# schematic.net
KiCad netlist of a schematic drawn in EAGLE
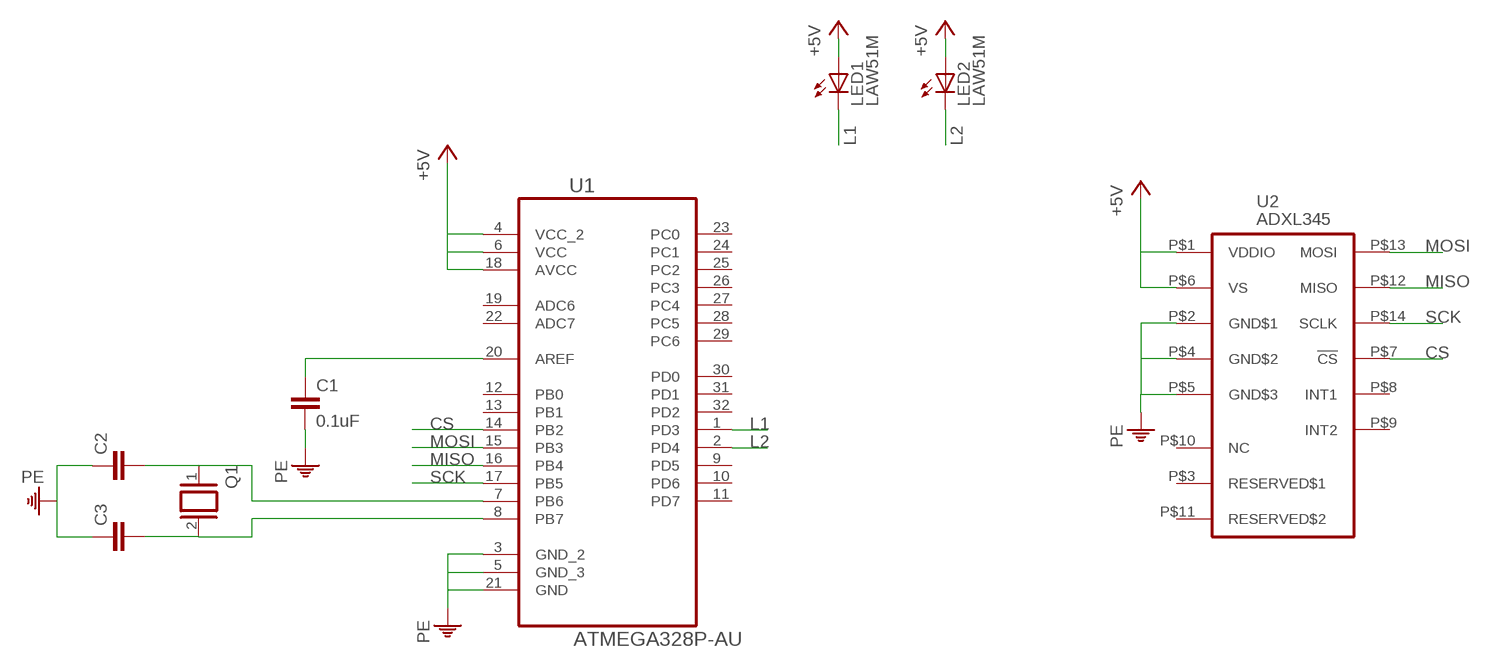
[diagram p0: schematic, sheet 1]

(export (version "E")
  (design (tool "Eeschema 10.0.6"))
  (components
    (comp (ref "C1")
      (value "0.1uF")
      (footprint "eagle-import:C2.5-3")
      (libsource (lib "eagle-import") (part "C2,5-3"))
    )
    (comp (ref "C2")
      (value "C2,5-3")
      (footprint "eagle-import:C2.5-3")
      (libsource (lib "eagle-import") (part "C2,5-3"))
    )
    (comp (ref "C3")
      (value "C2,5-3")
      (footprint "eagle-import:C2.5-3")
      (libsource (lib "eagle-import") (part "C2,5-3"))
    )
    (comp (ref "LED1")
      (value "LAW51M")
      (footprint "eagle-import:W51")
      (libsource (lib "eagle-import") (part "W51MLA"))
    )
    (comp (ref "LED2")
      (value "LAW51M")
      (footprint "eagle-import:W51")
      (libsource (lib "eagle-import") (part "W51MLA"))
    )
    (comp (ref "Q1")
      (value "XTAL/S")
      (footprint "eagle-import:QS")
      (libsource (lib "eagle-import") (part "XTAL/S"))
    )
    (comp (ref "U1")
      (value "ATMEGA328P-AU")
      (footprint "eagle-import:QFP80P900X900X120-32N")
      (libsource (lib "eagle-import") (part "ATMEGA328P-AU"))
    )
    (comp (ref "U2")
      (value "ADXL345")
      (footprint "eagle-import:LGA14")
      (libsource (lib "eagle-import") (part "ADXL345"))
    )
  )
  (nets
    (net (code "1") (name "+5V") (class "Default")
      (node (ref "LED1") (pin "A") (pinfunction "A_A") (pintype "passive"))
      (node (ref "LED2") (pin "A") (pinfunction "A_A") (pintype "passive"))
      (node (ref "U1") (pin "18") (pinfunction "AVCC_18") (pintype "power_in"))
      (node (ref "U1") (pin "4") (pinfunction "VCC_2_4") (pintype "power_in"))
      (node (ref "U1") (pin "6") (pinfunction "VCC_6") (pintype "power_in"))
      (node (ref "U2") (pin "P$1") (pinfunction "VDDIO_P$1") (pintype "power_in"))
      (node (ref "U2") (pin "P$6") (pinfunction "VS_P$6") (pintype "power_in"))
    )
    (net (code "2") (name "/CS") (class "Default")
      (node (ref "U1") (pin "14") (pinfunction "PB2_14") (pintype "bidirectional"))
      (node (ref "U2") (pin "P$7") (pinfunction "~{CS}_P$7") (pintype "input"))
    )
    (net (code "3") (name "/L1") (class "Default")
      (node (ref "LED1") (pin "C") (pinfunction "C_C") (pintype "passive"))
      (node (ref "U1") (pin "1") (pinfunction "PD3_1") (pintype "bidirectional"))
    )
    (net (code "4") (name "/L2") (class "Default")
      (node (ref "LED2") (pin "C") (pinfunction "C_C") (pintype "passive"))
      (node (ref "U1") (pin "2") (pinfunction "PD4_2") (pintype "bidirectional"))
    )
    (net (code "5") (name "/MISO") (class "Default")
      (node (ref "U1") (pin "16") (pinfunction "PB4_16") (pintype "bidirectional"))
      (node (ref "U2") (pin "P$12") (pinfunction "MISO_P$12") (pintype "output"))
    )
    (net (code "6") (name "/MOSI") (class "Default")
      (node (ref "U1") (pin "15") (pinfunction "PB3_15") (pintype "bidirectional"))
      (node (ref "U2") (pin "P$13") (pinfunction "MOSI_P$13") (pintype "input"))
    )
    (net (code "7") (name "/SCK") (class "Default")
      (node (ref "U1") (pin "17") (pinfunction "PB5_17") (pintype "bidirectional"))
      (node (ref "U2") (pin "P$14") (pinfunction "SCLK_P$14") (pintype "input"))
    )
    (net (code "8") (name "Net-(U1-AREF)") (class "Default")
      (node (ref "C1") (pin "1") (pinfunction "1_1") (pintype "passive"))
      (node (ref "U1") (pin "20") (pinfunction "AREF_20") (pintype "input"))
    )
    (net (code "9") (name "Net-(U1-PB6)") (class "Default")
      (node (ref "C2") (pin "2") (pinfunction "2_2") (pintype "passive"))
      (node (ref "Q1") (pin "1") (pinfunction "1_1") (pintype "passive"))
      (node (ref "U1") (pin "7") (pinfunction "PB6_7") (pintype "bidirectional"))
    )
    (net (code "10") (name "Net-(U1-PB7)") (class "Default")
      (node (ref "C3") (pin "2") (pinfunction "2_2") (pintype "passive"))
      (node (ref "Q1") (pin "2") (pinfunction "2_2") (pintype "passive"))
      (node (ref "U1") (pin "8") (pinfunction "PB7_8") (pintype "bidirectional"))
    )
    (net (code "11") (name "PE") (class "Default")
      (node (ref "C1") (pin "2") (pinfunction "2_2") (pintype "passive"))
      (node (ref "C2") (pin "1") (pinfunction "1_1") (pintype "passive"))
      (node (ref "C3") (pin "1") (pinfunction "1_1") (pintype "passive"))
      (node (ref "U1") (pin "21") (pinfunction "GND_21") (pintype "passive"))
      (node (ref "U1") (pin "3") (pinfunction "GND_2_3") (pintype "passive"))
      (node (ref "U1") (pin "5") (pinfunction "GND_3_5") (pintype "passive"))
      (node (ref "U2") (pin "P$2") (pinfunction "GND$1_P$2") (pintype "power_in"))
      (node (ref "U2") (pin "P$4") (pinfunction "GND$2_P$4") (pintype "power_in"))
      (node (ref "U2") (pin "P$5") (pinfunction "GND$3_P$5") (pintype "power_in"))
    )
    (net (code "12") (name "unconnected-(U1-ADC6-Pad19)") (class "Default")
      (node (ref "U1") (pin "19") (pinfunction "ADC6_19") (pintype "input"))
    )
    (net (code "13") (name "unconnected-(U1-ADC7-Pad22)") (class "Default")
      (node (ref "U1") (pin "22") (pinfunction "ADC7_22") (pintype "input"))
    )
    (net (code "14") (name "unconnected-(U1-PB0-Pad12)") (class "Default")
      (node (ref "U1") (pin "12") (pinfunction "PB0_12") (pintype "bidirectional"))
    )
    (net (code "15") (name "unconnected-(U1-PB1-Pad13)") (class "Default")
      (node (ref "U1") (pin "13") (pinfunction "PB1_13") (pintype "bidirectional"))
    )
    (net (code "16") (name "unconnected-(U1-PC0-Pad23)") (class "Default")
      (node (ref "U1") (pin "23") (pinfunction "PC0_23") (pintype "bidirectional"))
    )
    (net (code "17") (name "unconnected-(U1-PC1-Pad24)") (class "Default")
      (node (ref "U1") (pin "24") (pinfunction "PC1_24") (pintype "bidirectional"))
    )
    (net (code "18") (name "unconnected-(U1-PC2-Pad25)") (class "Default")
      (node (ref "U1") (pin "25") (pinfunction "PC2_25") (pintype "bidirectional"))
    )
    (net (code "19") (name "unconnected-(U1-PC3-Pad26)") (class "Default")
      (node (ref "U1") (pin "26") (pinfunction "PC3_26") (pintype "bidirectional"))
    )
    (net (code "20") (name "unconnected-(U1-PC4-Pad27)") (class "Default")
      (node (ref "U1") (pin "27") (pinfunction "PC4_27") (pintype "bidirectional"))
    )
    (net (code "21") (name "unconnected-(U1-PC5-Pad28)") (class "Default")
      (node (ref "U1") (pin "28") (pinfunction "PC5_28") (pintype "bidirectional"))
    )
    (net (code "22") (name "unconnected-(U1-PC6-Pad29)") (class "Default")
      (node (ref "U1") (pin "29") (pinfunction "PC6_29") (pintype "bidirectional"))
    )
    (net (code "23") (name "unconnected-(U1-PD0-Pad30)") (class "Default")
      (node (ref "U1") (pin "30") (pinfunction "PD0_30") (pintype "bidirectional"))
    )
    (net (code "24") (name "unconnected-(U1-PD1-Pad31)") (class "Default")
      (node (ref "U1") (pin "31") (pinfunction "PD1_31") (pintype "bidirectional"))
    )
    (net (code "25") (name "unconnected-(U1-PD2-Pad32)") (class "Default")
      (node (ref "U1") (pin "32") (pinfunction "PD2_32") (pintype "bidirectional"))
    )
    (net (code "26") (name "unconnected-(U1-PD5-Pad9)") (class "Default")
      (node (ref "U1") (pin "9") (pinfunction "PD5_9") (pintype "bidirectional"))
    )
    (net (code "27") (name "unconnected-(U1-PD6-Pad10)") (class "Default")
      (node (ref "U1") (pin "10") (pinfunction "PD6_10") (pintype "bidirectional"))
    )
    (net (code "28") (name "unconnected-(U1-PD7-Pad11)") (class "Default")
      (node (ref "U1") (pin "11") (pinfunction "PD7_11") (pintype "bidirectional"))
    )
    (net (code "29") (name "unconnected-(U2-INT1-PadP$8)") (class "Default")
      (node (ref "U2") (pin "P$8") (pinfunction "INT1_P$8") (pintype "output"))
    )
    (net (code "30") (name "unconnected-(U2-INT2-PadP$9)") (class "Default")
      (node (ref "U2") (pin "P$9") (pinfunction "INT2_P$9") (pintype "output"))
    )
    (net (code "31") (name "unconnected-(U2-NC-PadP$10)") (class "Default")
      (node (ref "U2") (pin "P$10") (pinfunction "NC_P$10") (pintype "bidirectional"))
    )
    (net (code "32") (name "unconnected-(U2-RESERVED$1-PadP$3)") (class "Default")
      (node (ref "U2") (pin "P$3") (pinfunction "RESERVED$1_P$3") (pintype "bidirectional"))
    )
    (net (code "33") (name "unconnected-(U2-RESERVED$2-PadP$11)") (class "Default")
      (node (ref "U2") (pin "P$11") (pinfunction "RESERVED$2_P$11") (pintype "bidirectional"))
    )
  )
)
